# Flow_sensor.net
KiCad netlist of a schematic drawn in Altium Designer
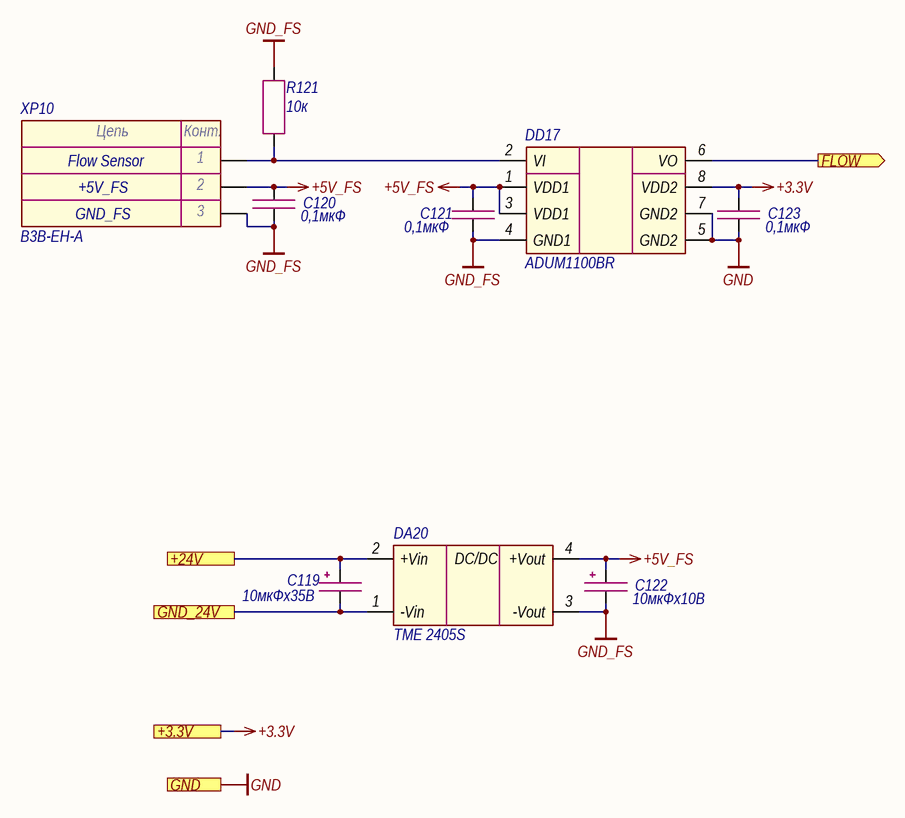
[diagram p0: Flow_sensor.SchDoc]

(export (version "E")
  (design (tool "Eeschema 10.0.6"))
  (components
    (comp (ref "C119")
      (value "10мкФх35B")
      (footprint "Pcb_library:CAP_C")
      (libsource (lib "Schem_library") (part "Capacitor_Polar"))
    )
    (comp (ref "C120")
      (value "0,1мкФ")
      (footprint "Pcb_library:CAP_0603")
      (fields (field (name "MANUFACTURER") "Murata"))
      (libsource (lib "Schem_library") (part "Capacitor"))
    )
    (comp (ref "C121")
      (value "0,1мкФ")
      (footprint "Pcb_library:CAP_0603")
      (fields (field (name "MANUFACTURER") "Murata"))
      (libsource (lib "Schem_library") (part "Capacitor"))
    )
    (comp (ref "C122")
      (value "10мкФх10B")
      (footprint "Pcb_library:CAP_A")
      (libsource (lib "Schem_library") (part "Capacitor_Polar"))
    )
    (comp (ref "C123")
      (value "0,1мкФ")
      (footprint "Pcb_library:CAP_0603")
      (fields (field (name "MANUFACTURER") "Murata"))
      (libsource (lib "Schem_library") (part "Capacitor"))
    )
    (comp (ref "DA20")
      (value "TME 2405S")
      (footprint "Pcb_library:TME (SIP-4)")
      (fields (field (name "MANUFACTURER") "Traco Power"))
      (libsource (lib "Schem_library") (part "TME"))
    )
    (comp (ref "DD17")
      (value "ADUM1100BR")
      (footprint "Pcb_library:SOIC-8")
      (fields (field (name "MANUFACTURER") "Analog Devices"))
      (libsource (lib "Schem_library") (part "ADUM1100"))
    )
    (comp (ref "R121")
      (value "10к")
      (footprint "Pcb_library:RES_0603")
      (fields (field (name "MANUFACTURER") "Yageo"))
      (libsource (lib "Schem_library") (part "Resistor"))
    )
    (comp (ref "XP10")
      (value "B3B-EH-A")
      (footprint "B3B-EH-A")
      (fields (field (name "MANUFACTURER") "JST"))
      (libsource (lib "Schem_library") (part "Connector-3"))
    )
  )
  (nets
    (net (code "1") (name "+3.3V") (class "Default")
      (node (ref "C123") (pin "1") (pinfunction "1_1") (pintype "passive"))
      (node (ref "DD17") (pin "8") (pinfunction "VDD2_8") (pintype "passive"))
    )
    (net (code "2") (name "+5V_FS") (class "Default")
      (node (ref "C120") (pin "1") (pinfunction "1_1") (pintype "passive"))
      (node (ref "C121") (pin "1") (pinfunction "1_1") (pintype "passive"))
      (node (ref "C122") (pin "1") (pinfunction "1_1") (pintype "passive"))
      (node (ref "DA20") (pin "4") (pinfunction "+Vout_4") (pintype "passive"))
      (node (ref "DD17") (pin "1") (pinfunction "VDD1_1") (pintype "passive"))
      (node (ref "DD17") (pin "3") (pinfunction "VDD1_3") (pintype "passive"))
      (node (ref "XP10") (pin "2") (pintype "passive"))
    )
    (net (code "3") (name "/+24V") (class "Default")
      (node (ref "C119") (pin "1") (pinfunction "1_1") (pintype "passive"))
      (node (ref "DA20") (pin "2") (pinfunction "+Vin_2") (pintype "passive"))
    )
    (net (code "4") (name "/FLOW") (class "Default")
      (node (ref "DD17") (pin "6") (pinfunction "VO_6") (pintype "passive"))
    )
    (net (code "5") (name "/GND_24V") (class "Default")
      (node (ref "C119") (pin "2") (pinfunction "2_2") (pintype "passive"))
      (node (ref "DA20") (pin "1") (pinfunction "-Vin_1") (pintype "passive"))
    )
    (net (code "6") (name "GND") (class "Default")
      (node (ref "C123") (pin "2") (pinfunction "2_2") (pintype "passive"))
      (node (ref "DD17") (pin "5") (pinfunction "GND2_5") (pintype "passive"))
      (node (ref "DD17") (pin "7") (pinfunction "GND2_7") (pintype "passive"))
    )
    (net (code "7") (name "GND_FS") (class "Default")
      (node (ref "C120") (pin "2") (pinfunction "2_2") (pintype "passive"))
      (node (ref "C121") (pin "2") (pinfunction "2_2") (pintype "passive"))
      (node (ref "C122") (pin "2") (pinfunction "2_2") (pintype "passive"))
      (node (ref "DA20") (pin "3") (pinfunction "-Vout_3") (pintype "passive"))
      (node (ref "DD17") (pin "4") (pinfunction "GND1_4") (pintype "passive"))
      (node (ref "R121") (pin "2") (pinfunction "2_2") (pintype "passive"))
      (node (ref "XP10") (pin "3") (pintype "passive"))
    )
    (net (code "8") (name "Net-(DD17-VI)") (class "Default")
      (node (ref "DD17") (pin "2") (pinfunction "VI_2") (pintype "passive"))
      (node (ref "R121") (pin "1") (pinfunction "1_1") (pintype "passive"))
      (node (ref "XP10") (pin "1") (pintype "passive"))
    )
  )
)
